# funo.net
KiCad netlist of a schematic drawn in EAGLE
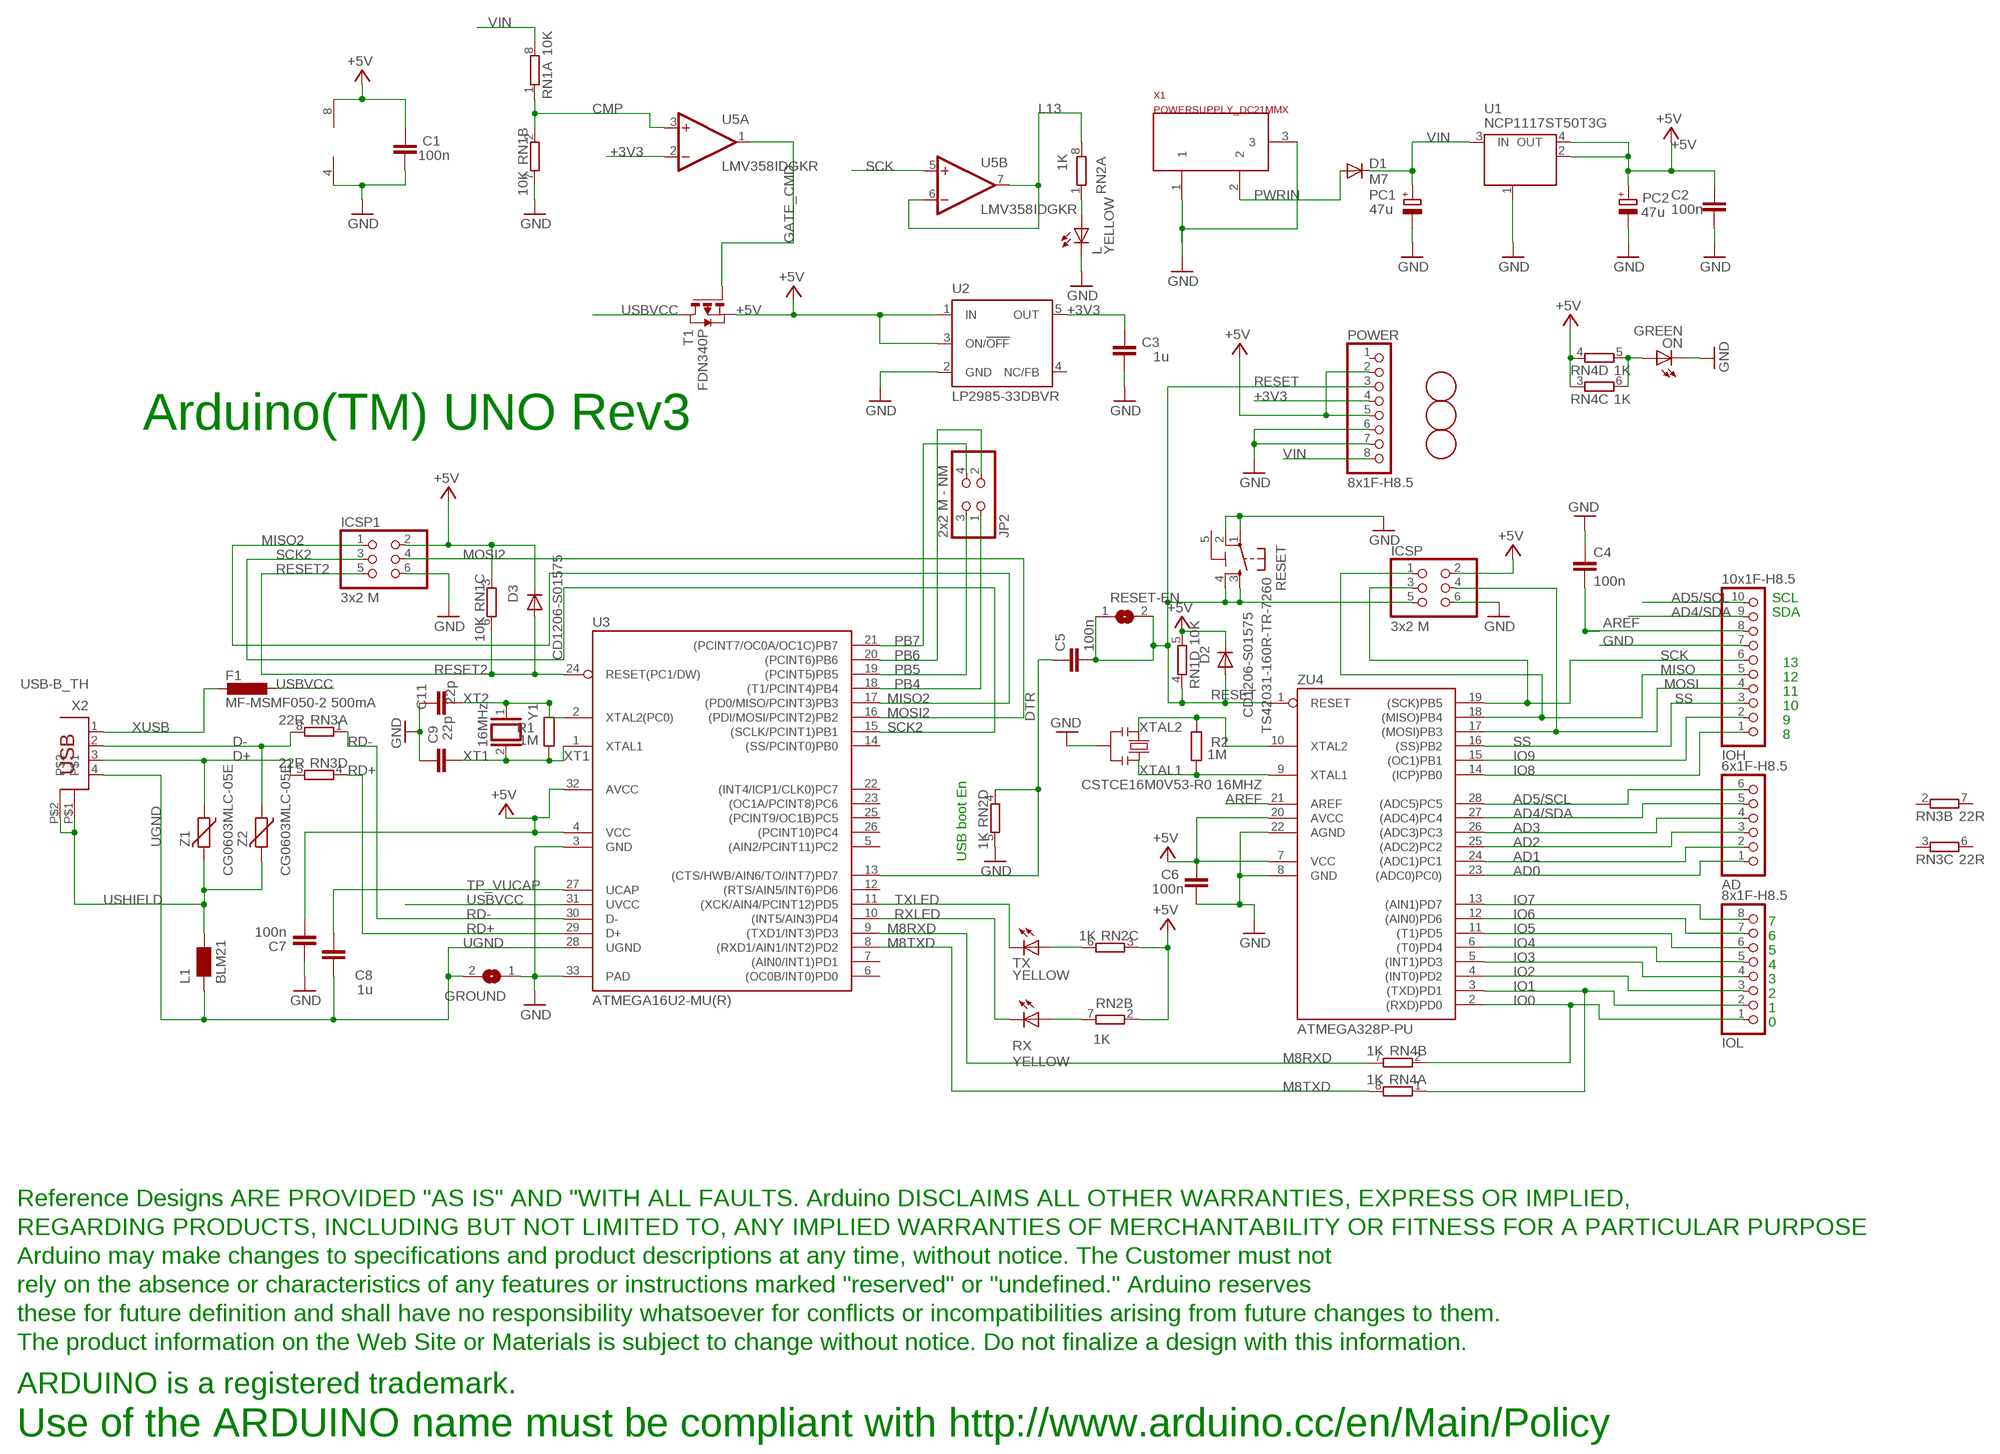
[diagram p0: schematic, sheet 1]

(export (version "E")
  (design (tool "Eeschema 10.0.6"))
  (components
    (comp (ref "AD")
      (value "6x1F-H8.5")
      (footprint "eagle-import:1X06")
      (libsource (lib "eagle-import") (part "PINHD-1X6"))
    )
    (comp (ref "C1")
      (value "100n")
      (footprint "eagle-import:C0603-ROUND")
      (libsource (lib "eagle-import") (part "C-EU0603-RND"))
    )
    (comp (ref "C2")
      (value "100n")
      (footprint "eagle-import:C0603-ROUND")
      (libsource (lib "eagle-import") (part "C-EU0603-RND"))
    )
    (comp (ref "C3")
      (value "1u")
      (footprint "eagle-import:C0603-ROUND")
      (libsource (lib "eagle-import") (part "C-EU0603-RND"))
    )
    (comp (ref "C4")
      (value "100n")
      (footprint "eagle-import:C0603-ROUND")
      (libsource (lib "eagle-import") (part "C-EU0603-RND"))
    )
    (comp (ref "C5")
      (value "100n")
      (footprint "eagle-import:C0603-ROUND")
      (libsource (lib "eagle-import") (part "C-EU0603-RND"))
    )
    (comp (ref "C6")
      (value "100n")
      (footprint "eagle-import:C0603-ROUND")
      (libsource (lib "eagle-import") (part "C-EU0603-RND"))
    )
    (comp (ref "C7")
      (value "100n")
      (footprint "eagle-import:C0603-ROUND")
      (libsource (lib "eagle-import") (part "C-EU0603-RND"))
    )
    (comp (ref "C8")
      (value "1u")
      (footprint "eagle-import:C0603-ROUND")
      (libsource (lib "eagle-import") (part "C-EU0603-RND"))
    )
    (comp (ref "C9")
      (value "22p")
      (footprint "eagle-import:C0603-ROUND")
      (libsource (lib "eagle-import") (part "C-EU0603-RND"))
    )
    (comp (ref "C11")
      (value "22p")
      (footprint "eagle-import:C0603-ROUND")
      (libsource (lib "eagle-import") (part "C-EU0603-RND"))
    )
    (comp (ref "D1")
      (value "M7")
      (footprint "eagle-import:SMB")
      (libsource (lib "eagle-import") (part "DIODE-SMB"))
    )
    (comp (ref "D2")
      (value "CD1206-S01575")
      (footprint "eagle-import:MINIMELF")
      (libsource (lib "eagle-import") (part "DIODE-MINIMELF"))
    )
    (comp (ref "D3")
      (value "CD1206-S01575")
      (footprint "eagle-import:MINIMELF")
      (libsource (lib "eagle-import") (part "DIODE-MINIMELF"))
    )
    (comp (ref "F1")
      (value "MF-MSMF050-2 500mA")
      (footprint "eagle-import:L1812")
      (libsource (lib "eagle-import") (part "L-EUL1812"))
    )
    (comp (ref "FD1")
      (value "FIDUCIALMOUNT")
      (footprint "eagle-import:FIDUCIA-MOUNT")
      (libsource (lib "eagle-import") (part "FIDUCIALMOUNT"))
    )
    (comp (ref "FD2")
      (value "FIDUCIALMOUNT")
      (footprint "eagle-import:FIDUCIA-MOUNT")
      (libsource (lib "eagle-import") (part "FIDUCIALMOUNT"))
    )
    (comp (ref "FD3")
      (value "FIDUCIALMOUNT")
      (footprint "eagle-import:FIDUCIA-MOUNT")
      (libsource (lib "eagle-import") (part "FIDUCIALMOUNT"))
    )
    (comp (ref "GROUND")
      (value "SJ")
      (footprint "eagle-import:SJ")
      (libsource (lib "eagle-import") (part "SJ"))
    )
    (comp (ref "ICSP")
      (value "3x2 M")
      (footprint "eagle-import:2X03")
      (libsource (lib "eagle-import") (part "PINHD-2X3"))
    )
    (comp (ref "ICSP1")
      (value "3x2 M")
      (footprint "eagle-import:2X03")
      (libsource (lib "eagle-import") (part "PINHD-2X3"))
    )
    (comp (ref "IOH")
      (value "10x1F-H8.5")
      (footprint "eagle-import:1X10")
      (libsource (lib "eagle-import") (part "PINHD-1X10_ARD"))
    )
    (comp (ref "IOL")
      (value "8x1F-H8.5")
      (footprint "eagle-import:1X08")
      (libsource (lib "eagle-import") (part "PINHD-1X8"))
    )
    (comp (ref "JP2")
      (value "2x2 M - NM")
      (footprint "eagle-import:2X02")
      (libsource (lib "eagle-import") (part "PINHD-2X2"))
    )
    (comp (ref "L")
      (value "YELLOW")
      (footprint "eagle-import:CHIP-LED0805")
      (libsource (lib "eagle-import") (part "LEDCHIP-LED0805"))
    )
    (comp (ref "L1")
      (value "BLM21")
      (footprint "eagle-import:0805")
      (libsource (lib "eagle-import") (part "WE-CBF_0805"))
    )
    (comp (ref "ON")
      (value "GREEN")
      (footprint "eagle-import:CHIP-LED0805")
      (libsource (lib "eagle-import") (part "LEDCHIP-LED0805"))
    )
    (comp (ref "PC1")
      (value "47u")
      (footprint "eagle-import:PANASONIC_D")
      (libsource (lib "eagle-import") (part "CPOL-EUD"))
    )
    (comp (ref "PC2")
      (value "47u")
      (footprint "eagle-import:PANASONIC_D")
      (libsource (lib "eagle-import") (part "CPOL-EUD"))
    )
    (comp (ref "POWER")
      (value "8x1F-H8.5")
      (footprint "eagle-import:1X08")
      (libsource (lib "eagle-import") (part "PINHD-1X8"))
    )
    (comp (ref "R1")
      (value "1M")
      (footprint "eagle-import:R0603-ROUND")
      (libsource (lib "eagle-import") (part "R-EU_R0603"))
    )
    (comp (ref "R2")
      (value "1M")
      (footprint "eagle-import:R0603-ROUND")
      (libsource (lib "eagle-import") (part "R-EU_R0603"))
    )
    (comp (ref "RESET")
      (value "TS42031-160R-TR-7260")
      (footprint "eagle-import:TS42")
      (libsource (lib "eagle-import") (part "TS42"))
    )
    (comp (ref "RESET-EN")
      (value "SJ")
      (footprint "eagle-import:SJ")
      (libsource (lib "eagle-import") (part "SJ"))
    )
    (comp (ref "RN1")
      (value "10K")
      (footprint "eagle-import:CAY16")
      (libsource (lib "eagle-import") (part "4R-NCAY16"))
    )
    (comp (ref "RN2")
      (value "1K")
      (footprint "eagle-import:CAY16")
      (libsource (lib "eagle-import") (part "4R-NCAY16"))
    )
    (comp (ref "RN3")
      (value "22R")
      (footprint "eagle-import:CAY16")
      (libsource (lib "eagle-import") (part "4R-NCAY16"))
    )
    (comp (ref "RN4")
      (value "1K")
      (footprint "eagle-import:CAY16")
      (libsource (lib "eagle-import") (part "4R-NCAY16"))
    )
    (comp (ref "RX")
      (value "YELLOW")
      (footprint "eagle-import:CHIP-LED0805")
      (libsource (lib "eagle-import") (part "LEDCHIP-LED0805"))
    )
    (comp (ref "T1")
      (value "FDN340P")
      (footprint "eagle-import:SOT-23")
      (libsource (lib "eagle-import") (part "PMOSSOT23"))
    )
    (comp (ref "TX")
      (value "YELLOW")
      (footprint "eagle-import:CHIP-LED0805")
      (libsource (lib "eagle-import") (part "LEDCHIP-LED0805"))
    )
    (comp (ref "U$1")
      (value "DISCLAIMER")
      (footprint "eagle-import:DISCLAIMER")
      (libsource (lib "eagle-import") (part "DISCLAIMER"))
    )
    (comp (ref "U1")
      (value "NCP1117ST50T3G")
      (footprint "eagle-import:SOT223")
      (libsource (lib "eagle-import") (part "MC33269ST-3.3T3"))
    )
    (comp (ref "U2")
      (value "LP2985-33DBVR")
      (footprint "eagle-import:SOT23-DBV")
      (libsource (lib "eagle-import") (part "LP2985-XXDBVR33"))
    )
    (comp (ref "U3")
      (value "ATMEGA16U2-MU(R)")
      (footprint "eagle-import:MLF32")
      (libsource (lib "eagle-import") (part "ATMEGA16U2-MU"))
    )
    (comp (ref "U5")
      (value "LMV358IDGKR")
      (footprint "eagle-import:MSOP08")
      (libsource (lib "eagle-import") (part "LMV358?MMX"))
    )
    (comp (ref "X1")
      (value "POWERSUPPLY_DC21MMX")
      (footprint "eagle-import:POWERSUPPLY_DC-21MM")
      (libsource (lib "eagle-import") (part "POWERSUPPLY_DC21MMX"))
    )
    (comp (ref "X2")
      (value "USB-B_TH")
      (footprint "eagle-import:PN61729")
      (libsource (lib "eagle-import") (part "PN61729"))
    )
    (comp (ref "Y1")
      (value "16MHz")
      (footprint "eagle-import:QS")
      (libsource (lib "eagle-import") (part "XTAL/S"))
    )
    (comp (ref "Y2")
      (value "CSTCE16M0V53-R0 16MHZ")
      (footprint "eagle-import:RESONATOR")
      (libsource (lib "eagle-import") (part "RESONATORMU"))
    )
    (comp (ref "Z1")
      (value "CG0603MLC-05E")
      (footprint "eagle-import:CT_CN0603")
      (libsource (lib "eagle-import") (part "VARISTORCN0603"))
    )
    (comp (ref "Z2")
      (value "CG0603MLC-05E")
      (footprint "eagle-import:CT_CN0603")
      (libsource (lib "eagle-import") (part "VARISTORCN0603"))
    )
    (comp (ref "ZU4")
      (value "ATMEGA328P-PU")
      (footprint "eagle-import:DIL28-3")
      (libsource (lib "eagle-import") (part "ATMEGA328P-PU"))
    )
  )
  (nets
    (net (code "1") (name "+5V") (class "Default")
      (node (ref "C1") (pin "2") (pinfunction "2_2") (pintype "passive"))
      (node (ref "C2") (pin "2") (pinfunction "2_2") (pintype "passive"))
      (node (ref "C6") (pin "2") (pinfunction "2_2") (pintype "passive"))
      (node (ref "C7") (pin "1") (pinfunction "1_1") (pintype "passive"))
      (node (ref "D2") (pin "C") (pinfunction "C_C") (pintype "passive"))
      (node (ref "D3") (pin "C") (pinfunction "C_C") (pintype "passive"))
      (node (ref "ICSP") (pin "2") (pinfunction "2_2") (pintype "passive"))
      (node (ref "ICSP1") (pin "2") (pinfunction "2_2") (pintype "passive"))
      (node (ref "PC2") (pin "+") (pinfunction "+_+") (pintype "passive"))
      (node (ref "POWER") (pin "2") (pinfunction "2_2") (pintype "passive"))
      (node (ref "POWER") (pin "5") (pinfunction "5_5") (pintype "passive"))
      (node (ref "RN1") (pin "3") (pinfunction "1_3") (pintype "passive"))
      (node (ref "RN1") (pin "5") (pinfunction "2_5") (pintype "passive"))
      (node (ref "RN2") (pin "2") (pinfunction "1_2") (pintype "passive"))
      (node (ref "RN2") (pin "3") (pinfunction "1_3") (pintype "passive"))
      (node (ref "RN4") (pin "3") (pinfunction "1_3") (pintype "passive"))
      (node (ref "RN4") (pin "4") (pinfunction "1_4") (pintype "passive"))
      (node (ref "T1") (pin "2") (pinfunction "S_2") (pintype "passive"))
      (node (ref "U1") (pin "2") (pinfunction "OUT_2") (pintype "passive"))
      (node (ref "U1") (pin "4") (pinfunction "OUT_4") (pintype "passive"))
      (node (ref "U2") (pin "1") (pinfunction "IN_1") (pintype "input"))
      (node (ref "U2") (pin "3") (pinfunction "ON/~{OFF}_3") (pintype "input"))
      (node (ref "U3") (pin "32") (pinfunction "AVCC_32") (pintype "power_in"))
      (node (ref "U3") (pin "4") (pinfunction "VCC_4") (pintype "power_in"))
      (node (ref "U5") (pin "8") (pinfunction "V+_8") (pintype "power_in"))
      (node (ref "ZU4") (pin "20") (pinfunction "AVCC_20") (pintype "power_in"))
      (node (ref "ZU4") (pin "7") (pinfunction "VCC_7") (pintype "power_in"))
    )
    (net (code "2") (name "/+3V3") (class "Default")
      (node (ref "C3") (pin "2") (pinfunction "2_2") (pintype "passive"))
      (node (ref "POWER") (pin "4") (pinfunction "4_4") (pintype "passive"))
      (node (ref "U2") (pin "5") (pinfunction "OUT_5") (pintype "passive"))
      (node (ref "U5") (pin "2") (pinfunction "-IN_2") (pintype "input"))
    )
    (net (code "3") (name "/5-GND") (class "Default")
      (node (ref "RESET") (pin "5") (pinfunction "5-GND_5") (pintype "power_in"))
    )
    (net (code "4") (name "/AD0") (class "Default")
      (node (ref "AD") (pin "1") (pinfunction "1_1") (pintype "passive"))
      (node (ref "ZU4") (pin "23") (pinfunction "(ADC0)PC0)_23") (pintype "bidirectional"))
    )
    (net (code "5") (name "/AD1") (class "Default")
      (node (ref "AD") (pin "2") (pinfunction "2_2") (pintype "passive"))
      (node (ref "ZU4") (pin "24") (pinfunction "(ADC1)PC1_24") (pintype "bidirectional"))
    )
    (net (code "6") (name "/AD2") (class "Default")
      (node (ref "AD") (pin "3") (pinfunction "3_3") (pintype "passive"))
      (node (ref "ZU4") (pin "25") (pinfunction "(ADC2)PC2_25") (pintype "bidirectional"))
    )
    (net (code "7") (name "/AD3") (class "Default")
      (node (ref "AD") (pin "4") (pinfunction "4_4") (pintype "passive"))
      (node (ref "ZU4") (pin "26") (pinfunction "(ADC3)PC3_26") (pintype "bidirectional"))
    )
    (net (code "8") (name "/AD4{slash}SDA") (class "Default")
      (node (ref "AD") (pin "5") (pinfunction "5_5") (pintype "passive"))
      (node (ref "IOH") (pin "9") (pinfunction "9_9") (pintype "passive"))
      (node (ref "ZU4") (pin "27") (pinfunction "(ADC4)PC4_27") (pintype "bidirectional"))
    )
    (net (code "9") (name "/AD5{slash}SCL") (class "Default")
      (node (ref "AD") (pin "6") (pinfunction "6_6") (pintype "passive"))
      (node (ref "IOH") (pin "10") (pinfunction "10_10") (pintype "passive"))
      (node (ref "ZU4") (pin "28") (pinfunction "(ADC5)PC5_28") (pintype "bidirectional"))
    )
    (net (code "10") (name "/AREF") (class "Default")
      (node (ref "C4") (pin "2") (pinfunction "2_2") (pintype "passive"))
      (node (ref "IOH") (pin "8") (pinfunction "8_8") (pintype "passive"))
      (node (ref "ZU4") (pin "21") (pinfunction "AREF_21") (pintype "passive"))
    )
    (net (code "11") (name "/CMP") (class "Default")
      (node (ref "RN1") (pin "1") (pinfunction "1_1") (pintype "passive"))
      (node (ref "RN1") (pin "2") (pinfunction "1_2") (pintype "passive"))
      (node (ref "U5") (pin "3") (pinfunction "+IN_3") (pintype "input"))
    )
    (net (code "12") (name "/D+") (class "Default")
      (node (ref "RN3") (pin "5") (pinfunction "2_5") (pintype "passive"))
      (node (ref "X2") (pin "3") (pinfunction "3_3") (pintype "bidirectional"))
      (node (ref "Z1") (pin "1") (pinfunction "1_1") (pintype "passive"))
    )
    (net (code "13") (name "/D-") (class "Default")
      (node (ref "RN3") (pin "8") (pinfunction "2_8") (pintype "passive"))
      (node (ref "X2") (pin "2") (pinfunction "2_2") (pintype "bidirectional"))
      (node (ref "Z2") (pin "1") (pinfunction "1_1") (pintype "passive"))
    )
    (net (code "14") (name "/DTR") (class "Default")
      (node (ref "C5") (pin "1") (pinfunction "1_1") (pintype "passive"))
      (node (ref "RN2") (pin "4") (pinfunction "1_4") (pintype "passive"))
      (node (ref "U3") (pin "13") (pinfunction "(CTS/HWB/AIN6/TO/INT7)PD7_13") (pintype "bidirectional"))
    )
    (net (code "15") (name "/GATE_CMD") (class "Default")
      (node (ref "T1") (pin "3") (pinfunction "G_3") (pintype "passive"))
      (node (ref "U5") (pin "1") (pinfunction "OUT_1") (pintype "output"))
    )
    (net (code "16") (name "/IO0") (class "Default")
      (node (ref "IOL") (pin "1") (pinfunction "1_1") (pintype "passive"))
      (node (ref "RN4") (pin "2") (pinfunction "1_2") (pintype "passive"))
      (node (ref "ZU4") (pin "2") (pinfunction "(RXD)PD0_2") (pintype "bidirectional"))
    )
    (net (code "17") (name "/IO1") (class "Default")
      (node (ref "IOL") (pin "2") (pinfunction "2_2") (pintype "passive"))
      (node (ref "RN4") (pin "1") (pinfunction "1_1") (pintype "passive"))
      (node (ref "ZU4") (pin "3") (pinfunction "(TXD)PD1_3") (pintype "bidirectional"))
    )
    (net (code "18") (name "/IO2") (class "Default")
      (node (ref "IOL") (pin "3") (pinfunction "3_3") (pintype "passive"))
      (node (ref "ZU4") (pin "4") (pinfunction "(INT0)PD2_4") (pintype "bidirectional"))
    )
    (net (code "19") (name "/IO3") (class "Default")
      (node (ref "IOL") (pin "4") (pinfunction "4_4") (pintype "passive"))
      (node (ref "ZU4") (pin "5") (pinfunction "(INT1)PD3_5") (pintype "bidirectional"))
    )
    (net (code "20") (name "/IO4") (class "Default")
      (node (ref "IOL") (pin "5") (pinfunction "5_5") (pintype "passive"))
      (node (ref "ZU4") (pin "6") (pinfunction "(T0)PD4_6") (pintype "bidirectional"))
    )
    (net (code "21") (name "/IO5") (class "Default")
      (node (ref "IOL") (pin "6") (pinfunction "6_6") (pintype "passive"))
      (node (ref "ZU4") (pin "11") (pinfunction "(T1)PD5_11") (pintype "bidirectional"))
    )
    (net (code "22") (name "/IO6") (class "Default")
      (node (ref "IOL") (pin "7") (pinfunction "7_7") (pintype "passive"))
      (node (ref "ZU4") (pin "12") (pinfunction "(AIN0)PD6_12") (pintype "bidirectional"))
    )
    (net (code "23") (name "/IO7") (class "Default")
      (node (ref "IOL") (pin "8") (pinfunction "8_8") (pintype "passive"))
      (node (ref "ZU4") (pin "13") (pinfunction "(AIN1)PD7_13") (pintype "bidirectional"))
    )
    (net (code "24") (name "/IO8") (class "Default")
      (node (ref "IOH") (pin "1") (pinfunction "1_1") (pintype "passive"))
      (node (ref "ZU4") (pin "14") (pinfunction "(ICP)PB0_14") (pintype "bidirectional"))
    )
    (net (code "25") (name "/IO9") (class "Default")
      (node (ref "IOH") (pin "2") (pinfunction "2_2") (pintype "passive"))
      (node (ref "ZU4") (pin "15") (pinfunction "(OC1)PB1_15") (pintype "bidirectional"))
    )
    (net (code "26") (name "/L13") (class "Default")
      (node (ref "RN2") (pin "8") (pinfunction "2_8") (pintype "passive"))
      (node (ref "U5") (pin "6") (pinfunction "-IN_6") (pintype "input"))
      (node (ref "U5") (pin "7") (pinfunction "OUT_7") (pintype "output"))
    )
    (net (code "27") (name "/M8RXD") (class "Default")
      (node (ref "RN4") (pin "7") (pinfunction "2_7") (pintype "passive"))
      (node (ref "U3") (pin "9") (pinfunction "(TXD1/INT3)PD3_9") (pintype "bidirectional"))
    )
    (net (code "28") (name "/M8TXD") (class "Default")
      (node (ref "RN4") (pin "8") (pinfunction "2_8") (pintype "passive"))
      (node (ref "U3") (pin "8") (pinfunction "(RXD1/AIN1/INT2)PD2_8") (pintype "bidirectional"))
    )
    (net (code "29") (name "/MISO") (class "Default")
      (node (ref "ICSP") (pin "1") (pinfunction "1_1") (pintype "passive"))
      (node (ref "IOH") (pin "5") (pinfunction "5_5") (pintype "passive"))
      (node (ref "ZU4") (pin "18") (pinfunction "(MISO)PB4_18") (pintype "bidirectional"))
    )
    (net (code "30") (name "/MISO2") (class "Default")
      (node (ref "ICSP1") (pin "1") (pinfunction "1_1") (pintype "passive"))
      (node (ref "U3") (pin "17") (pinfunction "(PD0/MISO/PCINT3)PB3_17") (pintype "bidirectional"))
    )
    (net (code "31") (name "/MOSI") (class "Default")
      (node (ref "ICSP") (pin "4") (pinfunction "4_4") (pintype "passive"))
      (node (ref "IOH") (pin "4") (pinfunction "4_4") (pintype "passive"))
      (node (ref "ZU4") (pin "17") (pinfunction "(MOSI)PB3_17") (pintype "bidirectional"))
    )
    (net (code "32") (name "/MOSI2") (class "Default")
      (node (ref "ICSP1") (pin "4") (pinfunction "4_4") (pintype "passive"))
      (node (ref "U3") (pin "16") (pinfunction "(PDI/MOSI/PCINT2)PB2_16") (pintype "bidirectional"))
    )
    (net (code "33") (name "/PB4") (class "Default")
      (node (ref "JP2") (pin "1") (pinfunction "1_1") (pintype "passive"))
      (node (ref "U3") (pin "18") (pinfunction "(T1/PCINT4)PB4_18") (pintype "bidirectional"))
    )
    (net (code "34") (name "/PB5") (class "Default")
      (node (ref "JP2") (pin "3") (pinfunction "3_3") (pintype "passive"))
      (node (ref "U3") (pin "19") (pinfunction "(PCINT5)PB5_19") (pintype "bidirectional"))
    )
    (net (code "35") (name "/PB6") (class "Default")
      (node (ref "JP2") (pin "2") (pinfunction "2_2") (pintype "passive"))
      (node (ref "U3") (pin "20") (pinfunction "(PCINT6)PB6_20") (pintype "bidirectional"))
    )
    (net (code "36") (name "/PB7") (class "Default")
      (node (ref "JP2") (pin "4") (pinfunction "4_4") (pintype "passive"))
      (node (ref "U3") (pin "21") (pinfunction "(PCINT7/OC0A/OC1C)PB7_21") (pintype "bidirectional"))
    )
    (net (code "37") (name "/PWRIN") (class "Default")
      (node (ref "D1") (pin "A") (pinfunction "A_A") (pintype "passive"))
      (node (ref "X1") (pin "2") (pinfunction "2_2") (pintype "power_in"))
    )
    (net (code "38") (name "/RD+") (class "Default")
      (node (ref "RN3") (pin "4") (pinfunction "1_4") (pintype "passive"))
      (node (ref "U3") (pin "29") (pinfunction "D+_29") (pintype "bidirectional"))
    )
    (net (code "39") (name "/RD-") (class "Default")
      (node (ref "RN3") (pin "1") (pinfunction "1_1") (pintype "passive"))
      (node (ref "U3") (pin "30") (pinfunction "D-_30") (pintype "bidirectional"))
    )
    (net (code "40") (name "/RESET") (class "Default")
      (node (ref "C5") (pin "2") (pinfunction "2_2") (pintype "passive"))
      (node (ref "D2") (pin "A") (pinfunction "A_A") (pintype "passive"))
      (node (ref "ICSP") (pin "5") (pinfunction "5_5") (pintype "passive"))
      (node (ref "POWER") (pin "3") (pinfunction "3_3") (pintype "passive"))
      (node (ref "RESET") (pin "3") (pinfunction "3_3") (pintype "passive"))
      (node (ref "RESET") (pin "4") (pinfunction "4_4") (pintype "passive"))
      (node (ref "RESET-EN") (pin "1") (pinfunction "1_1") (pintype "passive"))
      (node (ref "RESET-EN") (pin "2") (pinfunction "2_2") (pintype "passive"))
      (node (ref "RN1") (pin "4") (pinfunction "1_4") (pintype "passive"))
      (node (ref "ZU4") (pin "1") (pinfunction "RESET_1") (pintype "input"))
    )
    (net (code "41") (name "/RESET2") (class "Default")
      (node (ref "D3") (pin "A") (pinfunction "A_A") (pintype "passive"))
      (node (ref "ICSP1") (pin "5") (pinfunction "5_5") (pintype "passive"))
      (node (ref "RN1") (pin "6") (pinfunction "2_6") (pintype "passive"))
      (node (ref "U3") (pin "24") (pinfunction "RESET(PC1/DW)_24") (pintype "input"))
    )
    (net (code "42") (name "/RXLED") (class "Default")
      (node (ref "RX") (pin "C") (pinfunction "C_C") (pintype "passive"))
      (node (ref "U3") (pin "10") (pinfunction "(INT5/AIN3)PD4_10") (pintype "bidirectional"))
    )
    (net (code "43") (name "/SCK") (class "Default")
      (node (ref "ICSP") (pin "3") (pinfunction "3_3") (pintype "passive"))
      (node (ref "IOH") (pin "6") (pinfunction "6_6") (pintype "passive"))
      (node (ref "U5") (pin "5") (pinfunction "+IN_5") (pintype "input"))
      (node (ref "ZU4") (pin "19") (pinfunction "(SCK)PB5_19") (pintype "bidirectional"))
    )
    (net (code "44") (name "/SCK2") (class "Default")
      (node (ref "ICSP1") (pin "3") (pinfunction "3_3") (pintype "passive"))
      (node (ref "U3") (pin "15") (pinfunction "(SCLK/PCINT1)PB1_15") (pintype "bidirectional"))
    )
    (net (code "45") (name "/SS") (class "Default")
      (node (ref "IOH") (pin "3") (pinfunction "3_3") (pintype "passive"))
      (node (ref "ZU4") (pin "16") (pinfunction "(SS)PB2_16") (pintype "bidirectional"))
    )
    (net (code "46") (name "/TP_VUCAP") (class "Default")
      (node (ref "C8") (pin "1") (pinfunction "1_1") (pintype "passive"))
      (node (ref "U3") (pin "27") (pinfunction "UCAP_27") (pintype "passive"))
    )
    (net (code "47") (name "/TXLED") (class "Default")
      (node (ref "TX") (pin "C") (pinfunction "C_C") (pintype "passive"))
      (node (ref "U3") (pin "11") (pinfunction "(XCK/AIN4/PCINT12)PD5_11") (pintype "bidirectional"))
    )
    (net (code "48") (name "/UGND") (class "Default")
      (node (ref "C8") (pin "2") (pinfunction "2_2") (pintype "passive"))
      (node (ref "GROUND") (pin "2") (pinfunction "2_2") (pintype "passive"))
      (node (ref "L1") (pin "1") (pinfunction "1_1") (pintype "passive"))
      (node (ref "U3") (pin "28") (pinfunction "UGND_28") (pintype "power_in"))
      (node (ref "X2") (pin "4") (pinfunction "4_4") (pintype "bidirectional"))
    )
    (net (code "49") (name "/USBVCC") (class "Default")
      (node (ref "F1") (pin "1") (pinfunction "1_1") (pintype "passive"))
      (node (ref "T1") (pin "1") (pinfunction "D_1") (pintype "passive"))
      (node (ref "U3") (pin "31") (pinfunction "UVCC_31") (pintype "power_in"))
    )
    (net (code "50") (name "/USHIELD") (class "Default")
      (node (ref "L1") (pin "2") (pinfunction "2_2") (pintype "passive"))
      (node (ref "X2") (pin "P$1") (pinfunction "P$1_P$1") (pintype "bidirectional"))
      (node (ref "X2") (pin "P$2") (pinfunction "P$2_P$2") (pintype "bidirectional"))
      (node (ref "Z1") (pin "2") (pinfunction "2_2") (pintype "passive"))
      (node (ref "Z2") (pin "2") (pinfunction "2_2") (pintype "passive"))
    )
    (net (code "51") (name "/VIN") (class "Default")
      (node (ref "D1") (pin "C") (pinfunction "C_C") (pintype "passive"))
      (node (ref "PC1") (pin "+") (pinfunction "+_+") (pintype "passive"))
      (node (ref "POWER") (pin "8") (pinfunction "8_8") (pintype "passive"))
      (node (ref "RN1") (pin "8") (pinfunction "2_8") (pintype "passive"))
      (node (ref "U1") (pin "3") (pinfunction "IN_3") (pintype "input"))
    )
    (net (code "52") (name "/XT1") (class "Default")
      (node (ref "C9") (pin "1") (pinfunction "1_1") (pintype "passive"))
      (node (ref "R1") (pin "1") (pinfunction "1_1") (pintype "passive"))
      (node (ref "U3") (pin "1") (pinfunction "XTAL1_1") (pintype "bidirectional"))
      (node (ref "Y1") (pin "2") (pinfunction "2_2") (pintype "passive"))
    )
    (net (code "53") (name "/XT2") (class "Default")
      (node (ref "C11") (pin "1") (pinfunction "1_1") (pintype "passive"))
      (node (ref "R1") (pin "2") (pinfunction "2_2") (pintype "passive"))
      (node (ref "U3") (pin "2") (pinfunction "XTAL2(PC0)_2") (pintype "bidirectional"))
      (node (ref "Y1") (pin "1") (pinfunction "1_1") (pintype "passive"))
    )
    (net (code "54") (name "/XTAL1") (class "Default")
      (node (ref "R2") (pin "1") (pinfunction "1_1") (pintype "passive"))
      (node (ref "Y2") (pin "3") (pinfunction "3_3") (pintype "passive"))
      (node (ref "ZU4") (pin "9") (pinfunction "XTAL1_9") (pintype "bidirectional"))
    )
    (net (code "55") (name "/XTAL2") (class "Default")
      (node (ref "R2") (pin "2") (pinfunction "2_2") (pintype "passive"))
      (node (ref "Y2") (pin "1") (pinfunction "1_1") (pintype "passive"))
      (node (ref "ZU4") (pin "10") (pinfunction "XTAL2_10") (pintype "bidirectional"))
    )
    (net (code "56") (name "/XUSB") (class "Default")
      (node (ref "F1") (pin "2") (pinfunction "2_2") (pintype "passive"))
      (node (ref "X2") (pin "1") (pinfunction "1_1") (pintype "bidirectional"))
    )
    (net (code "57") (name "GND") (class "Default")
      (node (ref "C1") (pin "1") (pinfunction "1_1") (pintype "passive"))
      (node (ref "C11") (pin "2") (pinfunction "2_2") (pintype "passive"))
      (node (ref "C2") (pin "1") (pinfunction "1_1") (pintype "passive"))
      (node (ref "C3") (pin "1") (pinfunction "1_1") (pintype "passive"))
      (node (ref "C4") (pin "1") (pinfunction "1_1") (pintype "passive"))
      (node (ref "C6") (pin "1") (pinfunction "1_1") (pintype "passive"))
      (node (ref "C7") (pin "2") (pinfunction "2_2") (pintype "passive"))
      (node (ref "C9") (pin "2") (pinfunction "2_2") (pintype "passive"))
      (node (ref "GROUND") (pin "1") (pinfunction "1_1") (pintype "passive"))
      (node (ref "ICSP") (pin "6") (pinfunction "6_6") (pintype "passive"))
      (node (ref "ICSP1") (pin "6") (pinfunction "6_6") (pintype "passive"))
      (node (ref "IOH") (pin "7") (pinfunction "7_7") (pintype "passive"))
      (node (ref "L") (pin "C") (pinfunction "C_C") (pintype "passive"))
      (node (ref "ON") (pin "C") (pinfunction "C_C") (pintype "passive"))
      (node (ref "PC1") (pin "-") (pinfunction "-_-") (pintype "passive"))
      (node (ref "PC2") (pin "-") (pinfunction "-_-") (pintype "passive"))
      (node (ref "POWER") (pin "6") (pinfunction "6_6") (pintype "passive"))
      (node (ref "POWER") (pin "7") (pinfunction "7_7") (pintype "passive"))
      (node (ref "RESET") (pin "1") (pinfunction "1_1") (pintype "passive"))
      (node (ref "RESET") (pin "2") (pinfunction "2_2") (pintype "passive"))
      (node (ref "RN1") (pin "7") (pinfunction "2_7") (pintype "passive"))
      (node (ref "RN2") (pin "5") (pinfunction "2_5") (pintype "passive"))
      (node (ref "U1") (pin "1") (pinfunction "GND/ADJ_1") (pintype "input"))
      (node (ref "U2") (pin "2") (pinfunction "GND_2") (pintype "power_in"))
      (node (ref "U3") (pin "3") (pinfunction "GND_3") (pintype "power_in"))
      (node (ref "U3") (pin "33") (pinfunction "PAD_33") (pintype "power_in"))
      (node (ref "U5") (pin "4") (pinfunction "V-_4") (pintype "power_in"))
      (node (ref "X1") (pin "1") (pinfunction "1_1") (pintype "power_in"))
      (node (ref "X1") (pin "3") (pinfunction "3_3") (pintype "power_in"))
      (node (ref "Y2") (pin "2") (pinfunction "2_2") (pintype "passive"))
      (node (ref "ZU4") (pin "22") (pinfunction "AGND_22") (pintype "power_in"))
      (node (ref "ZU4") (pin "8") (pinfunction "GND_8") (pintype "power_in"))
    )
    (net (code "58") (name "Net-(L-PadA)") (class "Default")
      (node (ref "L") (pin "A") (pinfunction "A_A") (pintype "passive"))
      (node (ref "RN2") (pin "1") (pinfunction "1_1") (pintype "passive"))
    )
    (net (code "59") (name "Net-(RN2B-2)") (class "Default")
      (node (ref "RN2") (pin "7") (pinfunction "2_7") (pintype "passive"))
      (node (ref "RX") (pin "A") (pinfunction "A_A") (pintype "passive"))
    )
    (net (code "60") (name "Net-(RN2C-2)") (class "Default")
      (node (ref "RN2") (pin "6") (pinfunction "2_6") (pintype "passive"))
      (node (ref "TX") (pin "A") (pinfunction "A_A") (pintype "passive"))
    )
    (net (code "61") (name "Net-(RN4C-2)") (class "Default")
      (node (ref "ON") (pin "A") (pinfunction "A_A") (pintype "passive"))
      (node (ref "RN4") (pin "5") (pinfunction "2_5") (pintype "passive"))
      (node (ref "RN4") (pin "6") (pinfunction "2_6") (pintype "passive"))
    )
    (net (code "62") (name "unconnected-(POWER-Pad1)") (class "Default")
      (node (ref "POWER") (pin "1") (pinfunction "1_1") (pintype "passive"))
    )
    (net (code "63") (name "unconnected-(RN3B-1-Pad2)") (class "Default")
      (node (ref "RN3") (pin "2") (pinfunction "1_2") (pintype "passive"))
    )
    (net (code "64") (name "unconnected-(RN3B-2-Pad7)") (class "Default")
      (node (ref "RN3") (pin "7") (pinfunction "2_7") (pintype "passive"))
    )
    (net (code "65") (name "unconnected-(RN3C-1-Pad3)") (class "Default")
      (node (ref "RN3") (pin "3") (pinfunction "1_3") (pintype "passive"))
    )
    (net (code "66") (name "unconnected-(RN3C-2-Pad6)") (class "Default")
      (node (ref "RN3") (pin "6") (pinfunction "2_6") (pintype "passive"))
    )
    (net (code "67") (name "unconnected-(U2-NC{slash}FB-Pad4)") (class "Default")
      (node (ref "U2") (pin "4") (pinfunction "NC/FB_4") (pintype "passive"))
    )
    (net (code "68") (name "unconnected-(U3-(AIN0{slash}INT1)PD1-Pad7)") (class "Default")
      (node (ref "U3") (pin "7") (pinfunction "(AIN0/INT1)PD1_7") (pintype "bidirectional"))
    )
    (net (code "69") (name "unconnected-(U3-(AIN2{slash}PCINT11)PC2-Pad5)") (class "Default")
      (node (ref "U3") (pin "5") (pinfunction "(AIN2/PCINT11)PC2_5") (pintype "bidirectional"))
    )
    (net (code "70") (name "unconnected-(U3-(INT4{slash}ICP1{slash}CLK0)PC7-Pad22)") (class "Default")
      (node (ref "U3") (pin "22") (pinfunction "(INT4/ICP1/CLK0)PC7_22") (pintype "bidirectional"))
    )
    (net (code "71") (name "unconnected-(U3-(OC0B{slash}INT0)PD0-Pad6)") (class "Default")
      (node (ref "U3") (pin "6") (pinfunction "(OC0B/INT0)PD0_6") (pintype "bidirectional"))
    )
    (net (code "72") (name "unconnected-(U3-(OC1A{slash}PCINT8)PC6-Pad23)") (class "Default")
      (node (ref "U3") (pin "23") (pinfunction "(OC1A/PCINT8)PC6_23") (pintype "bidirectional"))
    )
    (net (code "73") (name "unconnected-(U3-(PCINT9{slash}OC1B)PC5-Pad25)") (class "Default")
      (node (ref "U3") (pin "25") (pinfunction "(PCINT9/OC1B)PC5_25") (pintype "bidirectional"))
    )
    (net (code "74") (name "unconnected-(U3-(PCINT10)PC4-Pad26)") (class "Default")
      (node (ref "U3") (pin "26") (pinfunction "(PCINT10)PC4_26") (pintype "bidirectional"))
    )
    (net (code "75") (name "unconnected-(U3-(RTS{slash}AIN5{slash}INT6)PD6-Pad12)") (class "Default")
      (node (ref "U3") (pin "12") (pinfunction "(RTS/AIN5/INT6)PD6_12") (pintype "bidirectional"))
    )
    (net (code "76") (name "unconnected-(U3-(SS{slash}PCINT0)PB0-Pad14)") (class "Default")
      (node (ref "U3") (pin "14") (pinfunction "(SS/PCINT0)PB0_14") (pintype "bidirectional"))
    )
  )
)
